# power_3V3.net
KiCad netlist of a schematic drawn in Altium Designer
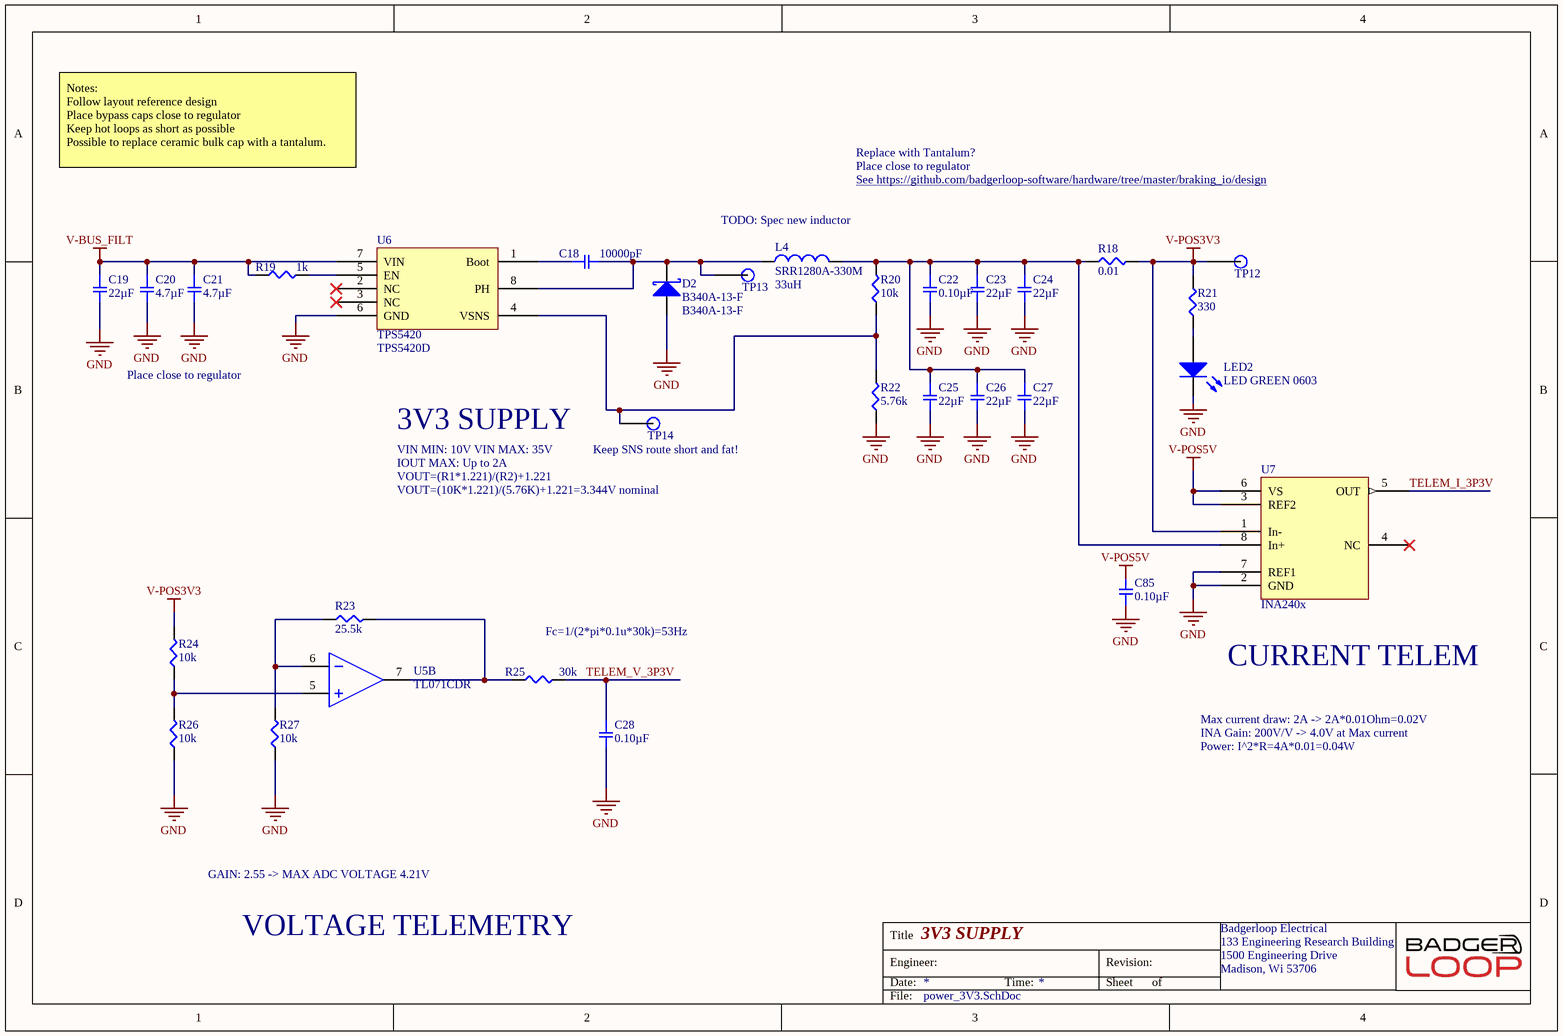
[diagram p0: power_3V3.SchDoc]

(export (version "E")
  (design (tool "Eeschema 10.0.6"))
  (components
    (comp (ref "C18")
      (value "10000pF")
      (footprint "SMD-0805C")
      (description "CAP CER 10000PF 250V X7T 0805")
      (fields
        (field (name "DIGI-KEY PART NUMBER") "490-13986-1-ND")
        (field (name "PART NUMBER") "GC321AD72E103KX01D")
      )
      (libsource (lib "capacitors") (part "GC321AD72E103KX01D"))
    )
    (comp (ref "C19")
      (value "22µF")
      (footprint "SMD-1206C")
      (description "CAP CER 22UF 25V X5R 1206")
      (fields
        (field (name "DIGI-KEY PART NUMBER") "490-12451-1-ND")
        (field (name "PART NUMBER") "GRT31CR61E226ME01L")
      )
      (libsource (lib "capacitors") (part "GRT31CR61E226ME01L"))
    )
    (comp (ref "C20")
      (value "4.7µF")
      (footprint "SMD-1206C")
      (description "CAP CER 4.7UF 50V X7S 1206")
      (fields
        (field (name "DIGI-KEY PART NUMBER") "490-11167-1-ND")
        (field (name "PART NUMBER") "GCM31CC71H475KA03L")
      )
      (libsource (lib "capacitors") (part "GCM31CC71H475KA03L"))
    )
    (comp (ref "C21")
      (value "4.7µF")
      (footprint "SMD-1206C")
      (description "CAP CER 4.7UF 50V X7S 1206")
      (fields
        (field (name "DIGI-KEY PART NUMBER") "490-11167-1-ND")
        (field (name "PART NUMBER") "GCM31CC71H475KA03L")
      )
      (libsource (lib "capacitors") (part "GCM31CC71H475KA03L"))
    )
    (comp (ref "C22")
      (value "0.10µF")
      (footprint "SMD-0805C")
      (description "CAP CER 0.1UF 10V U2J 0805")
      (fields
        (field (name "DIGI-KEY PART NUMBER") "490-11592-1-ND")
        (field (name "PART NUMBER") "GRM21B7U1A104JA01L")
      )
      (libsource (lib "capacitors") (part "GRM21B7U1A104JA01L"))
    )
    (comp (ref "C23")
      (value "22µF")
      (footprint "SMD-1206C")
      (description "CAP CER 22UF 25V X5R 1206")
      (fields
        (field (name "DIGI-KEY PART NUMBER") "490-12451-1-ND")
        (field (name "PART NUMBER") "GRT31CR61E226ME01L")
      )
      (libsource (lib "capacitors") (part "GRT31CR61E226ME01L"))
    )
    (comp (ref "C24")
      (value "22µF")
      (footprint "SMD-1206C")
      (description "CAP CER 22UF 25V X5R 1206")
      (fields
        (field (name "DIGI-KEY PART NUMBER") "490-12451-1-ND")
        (field (name "PART NUMBER") "GRT31CR61E226ME01L")
      )
      (libsource (lib "capacitors") (part "GRT31CR61E226ME01L"))
    )
    (comp (ref "C25")
      (value "22µF")
      (footprint "SMD-1206C")
      (description "CAP CER 22UF 25V X5R 1206")
      (fields
        (field (name "DIGI-KEY PART NUMBER") "490-12451-1-ND")
        (field (name "PART NUMBER") "GRT31CR61E226ME01L")
      )
      (libsource (lib "capacitors") (part "GRT31CR61E226ME01L"))
    )
    (comp (ref "C26")
      (value "22µF")
      (footprint "SMD-1206C")
      (description "CAP CER 22UF 25V X5R 1206")
      (fields
        (field (name "DIGI-KEY PART NUMBER") "490-12451-1-ND")
        (field (name "PART NUMBER") "GRT31CR61E226ME01L")
      )
      (libsource (lib "capacitors") (part "GRT31CR61E226ME01L"))
    )
    (comp (ref "C27")
      (value "22µF")
      (footprint "SMD-1206C")
      (description "CAP CER 22UF 25V X5R 1206")
      (fields
        (field (name "DIGI-KEY PART NUMBER") "490-12451-1-ND")
        (field (name "PART NUMBER") "GRT31CR61E226ME01L")
      )
      (libsource (lib "capacitors") (part "GRT31CR61E226ME01L"))
    )
    (comp (ref "C28")
      (value "0.10µF")
      (footprint "SMD-0805C")
      (description "CAP CER 0.1UF 16V X7R 0805")
      (fields
        (field (name "DIGI-KEY PART NUMBER") "490-1683-1-ND")
        (field (name "PART NUMBER") "GRM219R71C104KA01D")
      )
      (libsource (lib "capacitors") (part "GRM219R71C104KA01D"))
    )
    (comp (ref "C85")
      (value "0.10µF")
      (footprint "SMD-0805C")
      (description "CAP CER 0.1UF 10V U2J 0805")
      (fields
        (field (name "DIGI-KEY PART NUMBER") "490-11592-1-ND")
        (field (name "PART NUMBER") "GRM21B7U1A104JA01L")
      )
      (libsource (lib "capacitors") (part "GRM21B7U1A104JA01L"))
    )
    (comp (ref "D2")
      (value "B340A-13-F")
      (footprint "DIOM4326X20N")
      (description "DIODE SCHOTTKY 40V 3A SMA")
      (fields
        (field (name "MANUFACTURER") "Diodes")
        (field (name "VOLTAGE") "40V")
        (field (name "MANUFACTURER PART NUMBER") "B340A-13-F")
      )
      (libsource (lib "misc") (part "B340A-13-F"))
    )
    (comp (ref "L4")
      (value "SRR1280A-330M")
      (footprint "INDM120125X75N")
      (description "Inductor Power Shielded Wirewound 33uH 20% 1KHz 28Q-Factor Ferrite 3.5A 57mOhm DCR Automotive T/R")
      (fields
        (field (name "MANUFACTURER") "Bourns")
        (field (name "TOLERANCE") "20%")
        (field (name "INDUCTANCE") "33uH")
      )
      (libsource (lib "misc") (part "SRR1280A-330M"))
    )
    (comp (ref "LED2")
      (value "LED GREEN 0603")
      (footprint "LED 0603 GREEN")
      (fields (field (name "MANUFACTURER") "Lite-On Inc."))
      (libsource (lib "misc") (part "LED GREEN 0603"))
    )
    (comp (ref "R18")
      (value "0.01")
      (footprint "SMD-1206-RES")
      (description "RES SMD 0.01 OHM 1% 1/2W 1206")
      (fields
        (field (name "PART NUMBER") "ERJ-MP2KF10MU")
        (field (name "DIGI-KEY PART NUMBER") "P19322CT-ND")
      )
      (libsource (lib "resistors") (part "ERJ-MP2KF10MU"))
    )
    (comp (ref "R19")
      (value "1k")
      (footprint "SMD-0805-RES")
      (description "RES SMD 1K OHM 5% 1/2W 0805")
      (fields
        (field (name "PART NUMBER") "ERJ-P06J102V")
        (field (name "DIGI-KEY PART NUMBER") "P1.0KADCT-ND")
      )
      (libsource (lib "resistors") (part "ERJ-P06J102V"))
    )
    (comp (ref "R20")
      (value "10k")
      (footprint "SMD-0805-RES")
      (description "RES SMD 10K OHM 5% 1/2W 0805")
      (fields (field (name "PART NUMBER") "ERJ-P06J103V") (field (name "DIGI-KEY PART NUMBER") "P10KADCT-ND"))
      (libsource (lib "resistors") (part "ERJ-P06J103V"))
    )
    (comp (ref "R21")
      (value "330")
      (footprint "SMD-0805-RES")
      (description "RES SMD 330 OHM 5% 1/2W 0805")
      (fields (field (name "PART NUMBER") "ERJ-P06J331V") (field (name "DIGI-KEY PART NUMBER") "P330ADCT-ND"))
      (libsource (lib "resistors") (part "ERJ-P06J331V"))
    )
    (comp (ref "R22")
      (value "5.76k")
      (footprint "SMD-0805-RES")
      (description "RES SMD 5.76K OHM 1% 1/8W 0805")
      (fields
        (field (name "PART NUMBER") "ERJ-6ENF5761V")
        (field (name "DIGI-KEY PART NUMBER") "P5.76KCCT-ND")
      )
      (libsource (lib "resistors") (part "ERJ-6ENF5761V"))
    )
    (comp (ref "R23")
      (value "25.5k")
      (footprint "SMD-0805-RES")
      (description "RES SMD 25.5K OHM 1% 1/8W 0805")
      (fields
        (field (name "PART NUMBER") "ERJ-6ENF2552V")
        (field (name "DIGI-KEY PART NUMBER") "P25.5KCCT-ND")
      )
      (libsource (lib "resistors") (part "ERJ-6ENF2552V"))
    )
    (comp (ref "R24")
      (value "10k")
      (footprint "SMD-0805-RES")
      (description "RES SMD 10K OHM 5% 1/2W 0805")
      (fields (field (name "PART NUMBER") "ERJ-P06J103V") (field (name "DIGI-KEY PART NUMBER") "P10KADCT-ND"))
      (libsource (lib "resistors") (part "ERJ-P06J103V"))
    )
    (comp (ref "R25")
      (value "30k")
      (footprint "SMD-0805-RES")
      (description "RES SMD 30K OHM 1% 1/8W 0805")
      (fields
        (field (name "PART NUMBER") "ERJ-6ENF3002V")
        (field (name "DIGI-KEY PART NUMBER") "P30.0KCCT-ND")
      )
      (libsource (lib "resistors") (part "ERJ-6ENF3002V"))
    )
    (comp (ref "R26")
      (value "10k")
      (footprint "SMD-0805-RES")
      (description "RES SMD 10K OHM 5% 1/2W 0805")
      (fields (field (name "PART NUMBER") "ERJ-P06J103V") (field (name "DIGI-KEY PART NUMBER") "P10KADCT-ND"))
      (libsource (lib "resistors") (part "ERJ-P06J103V"))
    )
    (comp (ref "R27")
      (value "10k")
      (footprint "SMD-0805-RES")
      (description "RES SMD 10K OHM 5% 1/2W 0805")
      (fields (field (name "PART NUMBER") "ERJ-P06J103V") (field (name "DIGI-KEY PART NUMBER") "P10KADCT-ND"))
      (libsource (lib "resistors") (part "ERJ-P06J103V"))
    )
    (comp (ref "TP12")
      (value "TP")
      (footprint "Test Point")
      (description "SMD TEST POINT")
      (libsource (lib "misc") (part "TP"))
    )
    (comp (ref "TP13")
      (value "TP")
      (footprint "Test Point")
      (description "SMD TEST POINT")
      (libsource (lib "misc") (part "TP"))
    )
    (comp (ref "TP14")
      (value "TP")
      (footprint "Test Point")
      (description "SMD TEST POINT")
      (libsource (lib "misc") (part "TP"))
    )
    (comp (ref "U5")
      (value "TL071CDR")
      (footprint "SOP127P600X175-8N")
      (description "IC OPAMP JFET 3MHZ 8SOIC")
      (fields (field (name "MANUFACTURER") "Texas Instruments"))
      (libsource (lib "ic") (part "TL071CDR"))
    )
    (comp (ref "U6")
      (value "TPS5420")
      (footprint "SOP127P600X175-8N")
      (fields
        (field (name "MANUFACTURER") "Texas Instruments")
        (field (name "MANUFACTURER PART NUMBER") "TPS5420D")
      )
      (libsource (lib "ic") (part "TPS5420"))
    )
    (comp (ref "U7")
      (value "INA240x")
      (footprint "SOIC127P600X175-8N")
      (description "IC AMP CURRENT SENSE 8-TSSOP")
      (fields (field (name "MANUFACTURER") "TI"))
      (libsource (lib "ic") (part "INA240x"))
    )
  )
  (nets
    (net (code "1") (name "/TELEM_I_3P3V") (class "Default")
      (node (ref "U7") (pin "5") (pinfunction "OUT_5") (pintype "output"))
    )
    (net (code "2") (name "/TELEM_V_3P3V") (class "Default")
      (node (ref "C28") (pin "1") (pinfunction "1_1") (pintype "passive"))
      (node (ref "R25") (pin "2") (pinfunction "2_2") (pintype "passive"))
    )
    (net (code "3") (name "GND") (class "Default")
      (node (ref "C19") (pin "2") (pinfunction "2_2") (pintype "passive"))
      (node (ref "C20") (pin "2") (pinfunction "2_2") (pintype "passive"))
      (node (ref "C21") (pin "2") (pinfunction "2_2") (pintype "passive"))
      (node (ref "C22") (pin "2") (pinfunction "2_2") (pintype "passive"))
      (node (ref "C23") (pin "2") (pinfunction "2_2") (pintype "passive"))
      (node (ref "C24") (pin "2") (pinfunction "2_2") (pintype "passive"))
      (node (ref "C25") (pin "2") (pinfunction "2_2") (pintype "passive"))
      (node (ref "C26") (pin "2") (pinfunction "2_2") (pintype "passive"))
      (node (ref "C27") (pin "2") (pinfunction "2_2") (pintype "passive"))
      (node (ref "C28") (pin "2") (pinfunction "2_2") (pintype "passive"))
      (node (ref "C85") (pin "1") (pinfunction "1_1") (pintype "passive"))
      (node (ref "D2") (pin "1") (pinfunction "A_1") (pintype "passive"))
      (node (ref "LED2") (pin "2") (pinfunction "K_2") (pintype "passive"))
      (node (ref "R22") (pin "1") (pinfunction "1_1") (pintype "passive"))
      (node (ref "R26") (pin "1") (pinfunction "1_1") (pintype "passive"))
      (node (ref "R27") (pin "1") (pinfunction "1_1") (pintype "passive"))
      (node (ref "U6") (pin "6") (pinfunction "GND_6") (pintype "passive"))
      (node (ref "U7") (pin "2") (pinfunction "GND_2") (pintype "power_in"))
      (node (ref "U7") (pin "7") (pinfunction "REF1_7") (pintype "passive"))
    )
    (net (code "4") (name "Net-(D2-K)") (class "Default")
      (node (ref "C18") (pin "2") (pinfunction "2_2") (pintype "passive"))
      (node (ref "D2") (pin "2") (pinfunction "K_2") (pintype "passive"))
      (node (ref "L4") (pin "1") (pinfunction "1_1") (pintype "passive"))
      (node (ref "TP13") (pin "1") (pinfunction "1_1") (pintype "passive"))
      (node (ref "U6") (pin "8") (pinfunction "PH_8") (pintype "passive"))
    )
    (net (code "5") (name "Net-(LED2-A)") (class "Default")
      (node (ref "LED2") (pin "1") (pinfunction "A_1") (pintype "passive"))
      (node (ref "R21") (pin "1") (pinfunction "1_1") (pintype "passive"))
    )
    (net (code "6") (name "Net-(U5B-IN+)") (class "Default")
      (node (ref "R24") (pin "1") (pinfunction "1_1") (pintype "passive"))
      (node (ref "R26") (pin "2") (pinfunction "2_2") (pintype "passive"))
      (node (ref "U5") (pin "5") (pinfunction "IN+_5") (pintype "passive"))
    )
    (net (code "7") (name "Net-(U5B-IN-)") (class "Default")
      (node (ref "R23") (pin "1") (pinfunction "1_1") (pintype "passive"))
      (node (ref "R27") (pin "2") (pinfunction "2_2") (pintype "passive"))
      (node (ref "U5") (pin "6") (pinfunction "IN-_6") (pintype "passive"))
    )
    (net (code "8") (name "Net-(U5B-OUT)") (class "Default")
      (node (ref "R23") (pin "2") (pinfunction "2_2") (pintype "passive"))
      (node (ref "R25") (pin "1") (pinfunction "1_1") (pintype "passive"))
      (node (ref "U5") (pin "7") (pinfunction "OUT_7") (pintype "passive"))
    )
    (net (code "9") (name "Net-(U6-Boot)") (class "Default")
      (node (ref "C18") (pin "1") (pinfunction "1_1") (pintype "passive"))
      (node (ref "U6") (pin "1") (pinfunction "Boot_1") (pintype "passive"))
    )
    (net (code "10") (name "Net-(U6-EN)") (class "Default")
      (node (ref "R19") (pin "2") (pinfunction "2_2") (pintype "passive"))
      (node (ref "U6") (pin "5") (pinfunction "EN_5") (pintype "passive"))
    )
    (net (code "11") (name "Net-(U6-VSNS)") (class "Default")
      (node (ref "R20") (pin "1") (pinfunction "1_1") (pintype "passive"))
      (node (ref "R22") (pin "2") (pinfunction "2_2") (pintype "passive"))
      (node (ref "TP14") (pin "1") (pinfunction "1_1") (pintype "passive"))
      (node (ref "U6") (pin "4") (pinfunction "VSNS_4") (pintype "power_in"))
    )
    (net (code "12") (name "Net-(U7-In+)") (class "Default")
      (node (ref "C22") (pin "1") (pinfunction "1_1") (pintype "passive"))
      (node (ref "C23") (pin "1") (pinfunction "1_1") (pintype "passive"))
      (node (ref "C24") (pin "1") (pinfunction "1_1") (pintype "passive"))
      (node (ref "C25") (pin "1") (pinfunction "1_1") (pintype "passive"))
      (node (ref "C26") (pin "1") (pinfunction "1_1") (pintype "passive"))
      (node (ref "C27") (pin "1") (pinfunction "1_1") (pintype "passive"))
      (node (ref "L4") (pin "2") (pinfunction "2_2") (pintype "passive"))
      (node (ref "R18") (pin "1") (pinfunction "1_1") (pintype "passive"))
      (node (ref "R20") (pin "2") (pinfunction "2_2") (pintype "passive"))
      (node (ref "U7") (pin "8") (pinfunction "In+_8") (pintype "passive"))
    )
    (net (code "13") (name "V-BUS_FILT") (class "Default")
      (node (ref "C19") (pin "1") (pinfunction "1_1") (pintype "passive"))
      (node (ref "C20") (pin "1") (pinfunction "1_1") (pintype "passive"))
      (node (ref "C21") (pin "1") (pinfunction "1_1") (pintype "passive"))
      (node (ref "R19") (pin "1") (pinfunction "1_1") (pintype "passive"))
      (node (ref "U6") (pin "7") (pinfunction "VIN_7") (pintype "passive"))
    )
    (net (code "14") (name "V-POS3V3") (class "Default")
      (node (ref "R18") (pin "2") (pinfunction "2_2") (pintype "passive"))
      (node (ref "R21") (pin "2") (pinfunction "2_2") (pintype "passive"))
      (node (ref "R24") (pin "2") (pinfunction "2_2") (pintype "passive"))
      (node (ref "TP12") (pin "1") (pinfunction "1_1") (pintype "passive"))
      (node (ref "U7") (pin "1") (pinfunction "In-_1") (pintype "passive"))
    )
    (net (code "15") (name "V-POS5V") (class "Default")
      (node (ref "C85") (pin "2") (pinfunction "2_2") (pintype "passive"))
      (node (ref "U7") (pin "3") (pinfunction "REF2_3") (pintype "passive"))
      (node (ref "U7") (pin "6") (pinfunction "VS_6") (pintype "power_in"))
    )
    (net (code "16") (name "unconnected-(U6-NC-Pad2)") (class "Default")
      (node (ref "U6") (pin "2") (pinfunction "NC_2") (pintype "power_in+no_connect"))
    )
    (net (code "17") (name "unconnected-(U6-NC-Pad3)") (class "Default")
      (node (ref "U6") (pin "3") (pinfunction "NC_3") (pintype "passive+no_connect"))
    )
    (net (code "18") (name "unconnected-(U7-NC-Pad4)") (class "Default")
      (node (ref "U7") (pin "4") (pinfunction "NC_4") (pintype "passive+no_connect"))
    )
  )
)
